# SCH.net
KiCad netlist of a schematic drawn in EAGLE
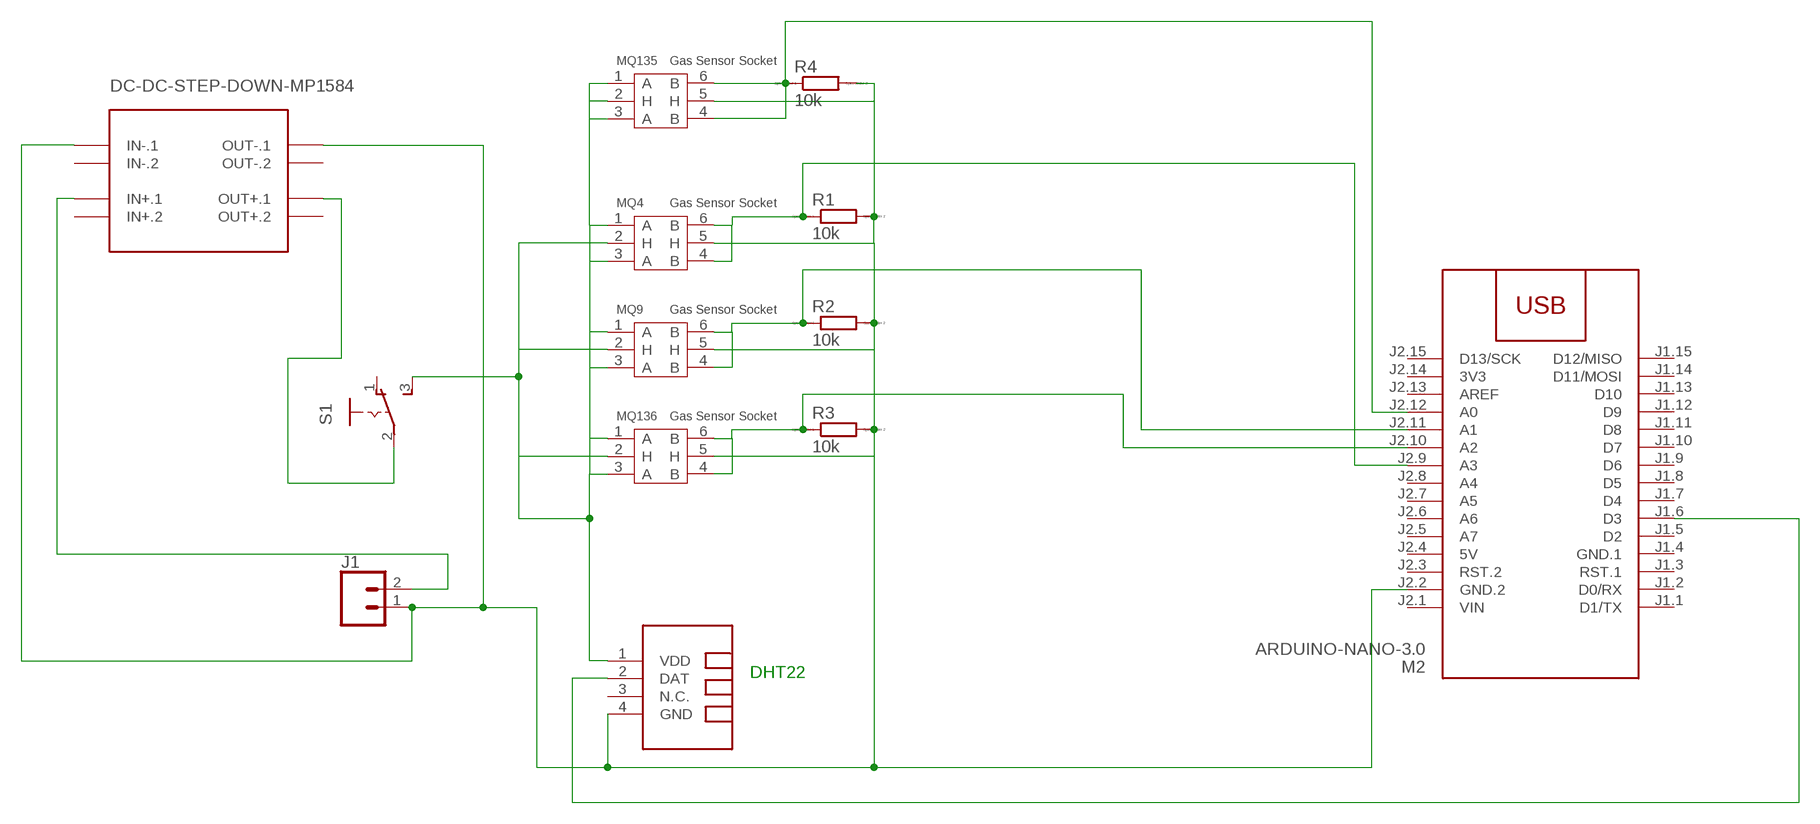
[diagram p0: schematic, sheet 1]

(export (version "E")
  (design (tool "Eeschema 10.0.6"))
  (components
    (comp (ref "J1")
      (value "CONN_021X02_NO_SILK")
      (footprint "eagle-import:1X02_NO_SILK")
      (libsource (lib "eagle-import") (part "CONN_021X02_NO_SILK"))
    )
    (comp (ref "M2")
      (value "ARDUINO-NANO-3.0")
      (footprint "eagle-import:ARDUINO-NANO-3.0")
      (libsource (lib "eagle-import") (part "ARDUINO-NANO-3.0"))
    )
    (comp (ref "MQ4")
      (value "Gas Sensor Socket")
      (footprint "eagle-import:6P-D17.6X9.8H")
      (libsource (lib "eagle-import") (part "MQ-SOCKET"))
    )
    (comp (ref "MQ9")
      (value "Gas Sensor Socket")
      (footprint "eagle-import:6P-D17.6X9.8H")
      (libsource (lib "eagle-import") (part "MQ-SOCKET"))
    )
    (comp (ref "MQ135")
      (value "Gas Sensor Socket")
      (footprint "eagle-import:6P-D17.6X9.8H")
      (libsource (lib "eagle-import") (part "MQ-SOCKET"))
    )
    (comp (ref "MQ136")
      (value "Gas Sensor Socket")
      (footprint "eagle-import:6P-D17.6X9.8H")
      (libsource (lib "eagle-import") (part "MQ-SOCKET"))
    )
    (comp (ref "R1")
      (value "10k")
      (footprint "eagle-import:0204_7")
      (libsource (lib "eagle-import") (part "R0204/7"))
    )
    (comp (ref "R2")
      (value "10k")
      (footprint "eagle-import:0204_7")
      (libsource (lib "eagle-import") (part "R0204/7"))
    )
    (comp (ref "R3")
      (value "10k")
      (footprint "eagle-import:0204_7")
      (libsource (lib "eagle-import") (part "R0204/7"))
    )
    (comp (ref "R4")
      (value "10k")
      (footprint "eagle-import:0204_7")
      (libsource (lib "eagle-import") (part "R0204/7"))
    )
    (comp (ref "S1")
      (value "255SB")
      (footprint "eagle-import:255SB")
      (libsource (lib "eagle-import") (part "255SB"))
    )
    (comp (ref "U$1")
      (value "TEMP-HUM-SENSOR-DHT22")
      (footprint "eagle-import:TEMP-HUM-SENSOR-DHT22")
      (libsource (lib "eagle-import") (part "TEMP-HUM-SENSOR-DHT22"))
    )
    (comp (ref "U$2")
      (value "DC-DC-STEP-DOWN-MP1584")
      (footprint "eagle-import:DC-DC-STEP-DOWN-MP1584")
      (libsource (lib "eagle-import") (part "DC-DC-STEP-DOWN-MP1584"))
    )
  )
  (nets
    (net (code "1") (name "/3V3") (class "Default")
      (node (ref "M2") (pin "J2.14") (pinfunction "3V3_J2.14") (pintype "power_in"))
    )
    (net (code "2") (name "/5V") (class "Default")
      (node (ref "M2") (pin "J2.4") (pinfunction "5V_J2.4") (pintype "power_in"))
    )
    (net (code "3") (name "/GND.1") (class "Default")
      (node (ref "M2") (pin "J1.4") (pinfunction "GND.1_J1.4") (pintype "power_in"))
    )
    (net (code "4") (name "/VIN") (class "Default")
      (node (ref "M2") (pin "J2.1") (pinfunction "VIN_J2.1") (pintype "power_in"))
    )
    (net (code "5") (name "Net-(J1-Pad2)") (class "Default")
      (node (ref "J1") (pin "2") (pinfunction "2_2") (pintype "passive"))
      (node (ref "U$2") (pin "IN+.1") (pinfunction "IN+.1_IN+.1") (pintype "bidirectional"))
    )
    (net (code "6") (name "Net-(M2-A0)") (class "Default")
      (node (ref "M2") (pin "J2.12") (pinfunction "A0_J2.12") (pintype "bidirectional"))
      (node (ref "MQ135") (pin "4") (pinfunction "B_4") (pintype "bidirectional"))
      (node (ref "MQ135") (pin "6") (pinfunction "B_6") (pintype "bidirectional"))
      (node (ref "R4") (pin "1") (pinfunction "1_1") (pintype "passive"))
    )
    (net (code "7") (name "Net-(M2-A1)") (class "Default")
      (node (ref "M2") (pin "J2.11") (pinfunction "A1_J2.11") (pintype "bidirectional"))
      (node (ref "MQ9") (pin "4") (pinfunction "B_4") (pintype "bidirectional"))
      (node (ref "MQ9") (pin "6") (pinfunction "B_6") (pintype "bidirectional"))
      (node (ref "R2") (pin "1") (pinfunction "1_1") (pintype "passive"))
    )
    (net (code "8") (name "Net-(M2-A2)") (class "Default")
      (node (ref "M2") (pin "J2.10") (pinfunction "A2_J2.10") (pintype "bidirectional"))
      (node (ref "MQ136") (pin "4") (pinfunction "B_4") (pintype "bidirectional"))
      (node (ref "MQ136") (pin "6") (pinfunction "B_6") (pintype "bidirectional"))
      (node (ref "R3") (pin "1") (pinfunction "1_1") (pintype "passive"))
    )
    (net (code "9") (name "Net-(M2-A3)") (class "Default")
      (node (ref "M2") (pin "J2.9") (pinfunction "A3_J2.9") (pintype "bidirectional"))
      (node (ref "MQ4") (pin "4") (pinfunction "B_4") (pintype "bidirectional"))
      (node (ref "MQ4") (pin "6") (pinfunction "B_6") (pintype "bidirectional"))
      (node (ref "R1") (pin "1") (pinfunction "1_1") (pintype "passive"))
    )
    (net (code "10") (name "Net-(M2-D3)") (class "Default")
      (node (ref "M2") (pin "J1.6") (pinfunction "D3_J1.6") (pintype "bidirectional"))
      (node (ref "U$1") (pin "2") (pinfunction "DAT_2") (pintype "bidirectional"))
    )
    (net (code "11") (name "Net-(M2-GND.2)") (class "Default")
      (node (ref "J1") (pin "1") (pinfunction "1_1") (pintype "passive"))
      (node (ref "M2") (pin "J2.2") (pinfunction "GND.2_J2.2") (pintype "power_in"))
      (node (ref "MQ135") (pin "5") (pinfunction "H_5") (pintype "bidirectional"))
      (node (ref "MQ136") (pin "5") (pinfunction "H_5") (pintype "bidirectional"))
      (node (ref "MQ4") (pin "5") (pinfunction "H_5") (pintype "bidirectional"))
      (node (ref "MQ9") (pin "5") (pinfunction "H_5") (pintype "bidirectional"))
      (node (ref "R1") (pin "2") (pinfunction "2_2") (pintype "passive"))
      (node (ref "R2") (pin "2") (pinfunction "2_2") (pintype "passive"))
      (node (ref "R3") (pin "2") (pinfunction "2_2") (pintype "passive"))
      (node (ref "R4") (pin "2") (pinfunction "2_2") (pintype "passive"))
      (node (ref "U$1") (pin "4") (pinfunction "GND_4") (pintype "power_in"))
      (node (ref "U$2") (pin "IN-.1") (pinfunction "IN-.1_IN-.1") (pintype "bidirectional"))
      (node (ref "U$2") (pin "OUT-.1") (pinfunction "OUT-.1_OUT-.1") (pintype "bidirectional"))
    )
    (net (code "12") (name "Net-(S1-P)") (class "Default")
      (node (ref "S1") (pin "2") (pinfunction "P_2") (pintype "passive"))
      (node (ref "U$2") (pin "OUT+.1") (pinfunction "OUT+.1_OUT+.1") (pintype "bidirectional"))
    )
    (net (code "13") (name "Net-(S1-S)") (class "Default")
      (node (ref "MQ135") (pin "1") (pinfunction "A_1") (pintype "bidirectional"))
      (node (ref "MQ135") (pin "2") (pinfunction "H_2") (pintype "bidirectional"))
      (node (ref "MQ135") (pin "3") (pinfunction "A_3") (pintype "bidirectional"))
      (node (ref "MQ136") (pin "1") (pinfunction "A_1") (pintype "bidirectional"))
      (node (ref "MQ136") (pin "2") (pinfunction "H_2") (pintype "bidirectional"))
      (node (ref "MQ136") (pin "3") (pinfunction "A_3") (pintype "bidirectional"))
      (node (ref "MQ4") (pin "1") (pinfunction "A_1") (pintype "bidirectional"))
      (node (ref "MQ4") (pin "2") (pinfunction "H_2") (pintype "bidirectional"))
      (node (ref "MQ4") (pin "3") (pinfunction "A_3") (pintype "bidirectional"))
      (node (ref "MQ9") (pin "1") (pinfunction "A_1") (pintype "bidirectional"))
      (node (ref "MQ9") (pin "2") (pinfunction "H_2") (pintype "bidirectional"))
      (node (ref "MQ9") (pin "3") (pinfunction "A_3") (pintype "bidirectional"))
      (node (ref "S1") (pin "3") (pinfunction "S_3") (pintype "passive"))
      (node (ref "U$1") (pin "1") (pinfunction "VDD_1") (pintype "power_in"))
    )
    (net (code "14") (name "unconnected-(M2-A4-PadJ2.8)") (class "Default")
      (node (ref "M2") (pin "J2.8") (pinfunction "A4_J2.8") (pintype "bidirectional"))
    )
    (net (code "15") (name "unconnected-(M2-A5-PadJ2.7)") (class "Default")
      (node (ref "M2") (pin "J2.7") (pinfunction "A5_J2.7") (pintype "bidirectional"))
    )
    (net (code "16") (name "unconnected-(M2-A6-PadJ2.6)") (class "Default")
      (node (ref "M2") (pin "J2.6") (pinfunction "A6_J2.6") (pintype "bidirectional"))
    )
    (net (code "17") (name "unconnected-(M2-A7-PadJ2.5)") (class "Default")
      (node (ref "M2") (pin "J2.5") (pinfunction "A7_J2.5") (pintype "bidirectional"))
    )
    (net (code "18") (name "unconnected-(M2-AREF-PadJ2.13)") (class "Default")
      (node (ref "M2") (pin "J2.13") (pinfunction "AREF_J2.13") (pintype "bidirectional"))
    )
    (net (code "19") (name "unconnected-(M2-D0{slash}RX-PadJ1.2)") (class "Default")
      (node (ref "M2") (pin "J1.2") (pinfunction "D0/RX_J1.2") (pintype "bidirectional"))
    )
    (net (code "20") (name "unconnected-(M2-D1{slash}TX-PadJ1.1)") (class "Default")
      (node (ref "M2") (pin "J1.1") (pinfunction "D1/TX_J1.1") (pintype "bidirectional"))
    )
    (net (code "21") (name "unconnected-(M2-D2-PadJ1.5)") (class "Default")
      (node (ref "M2") (pin "J1.5") (pinfunction "D2_J1.5") (pintype "bidirectional"))
    )
    (net (code "22") (name "unconnected-(M2-D4-PadJ1.7)") (class "Default")
      (node (ref "M2") (pin "J1.7") (pinfunction "D4_J1.7") (pintype "bidirectional"))
    )
    (net (code "23") (name "unconnected-(M2-D5-PadJ1.8)") (class "Default")
      (node (ref "M2") (pin "J1.8") (pinfunction "D5_J1.8") (pintype "bidirectional"))
    )
    (net (code "24") (name "unconnected-(M2-D6-PadJ1.9)") (class "Default")
      (node (ref "M2") (pin "J1.9") (pinfunction "D6_J1.9") (pintype "bidirectional"))
    )
    (net (code "25") (name "unconnected-(M2-D7-PadJ1.10)") (class "Default")
      (node (ref "M2") (pin "J1.10") (pinfunction "D7_J1.10") (pintype "bidirectional"))
    )
    (net (code "26") (name "unconnected-(M2-D8-PadJ1.11)") (class "Default")
      (node (ref "M2") (pin "J1.11") (pinfunction "D8_J1.11") (pintype "bidirectional"))
    )
    (net (code "27") (name "unconnected-(M2-D9-PadJ1.12)") (class "Default")
      (node (ref "M2") (pin "J1.12") (pinfunction "D9_J1.12") (pintype "bidirectional"))
    )
    (net (code "28") (name "unconnected-(M2-D10-PadJ1.13)") (class "Default")
      (node (ref "M2") (pin "J1.13") (pinfunction "D10_J1.13") (pintype "bidirectional"))
    )
    (net (code "29") (name "unconnected-(M2-D11{slash}MOSI-PadJ1.14)") (class "Default")
      (node (ref "M2") (pin "J1.14") (pinfunction "D11/MOSI_J1.14") (pintype "bidirectional"))
    )
    (net (code "30") (name "unconnected-(M2-D12{slash}MISO-PadJ1.15)") (class "Default")
      (node (ref "M2") (pin "J1.15") (pinfunction "D12/MISO_J1.15") (pintype "bidirectional"))
    )
    (net (code "31") (name "unconnected-(M2-D13{slash}SCK-PadJ2.15)") (class "Default")
      (node (ref "M2") (pin "J2.15") (pinfunction "D13/SCK_J2.15") (pintype "bidirectional"))
    )
    (net (code "32") (name "unconnected-(M2-RST.1-PadJ1.3)") (class "Default")
      (node (ref "M2") (pin "J1.3") (pinfunction "RST.1_J1.3") (pintype "bidirectional"))
    )
    (net (code "33") (name "unconnected-(M2-RST.2-PadJ2.3)") (class "Default")
      (node (ref "M2") (pin "J2.3") (pinfunction "RST.2_J2.3") (pintype "bidirectional"))
    )
    (net (code "34") (name "unconnected-(S1-O-Pad1)") (class "Default")
      (node (ref "S1") (pin "1") (pinfunction "O_1") (pintype "passive"))
    )
    (net (code "35") (name "unconnected-(U$1-N.C.-Pad3)") (class "Default")
      (node (ref "U$1") (pin "3") (pinfunction "N.C._3") (pintype "passive"))
    )
    (net (code "36") (name "unconnected-(U$2-PadIN+.2)") (class "Default")
      (node (ref "U$2") (pin "IN+.2") (pinfunction "IN+.2_IN+.2") (pintype "bidirectional"))
    )
    (net (code "37") (name "unconnected-(U$2-PadIN-.2)") (class "Default")
      (node (ref "U$2") (pin "IN-.2") (pinfunction "IN-.2_IN-.2") (pintype "bidirectional"))
    )
    (net (code "38") (name "unconnected-(U$2-PadOUT+.2)") (class "Default")
      (node (ref "U$2") (pin "OUT+.2") (pinfunction "OUT+.2_OUT+.2") (pintype "bidirectional"))
    )
    (net (code "39") (name "unconnected-(U$2-PadOUT-.2)") (class "Default")
      (node (ref "U$2") (pin "OUT-.2") (pinfunction "OUT-.2_OUT-.2") (pintype "bidirectional"))
    )
  )
)
